# PiezoDriver.net
KiCad netlist of a schematic drawn in EAGLE
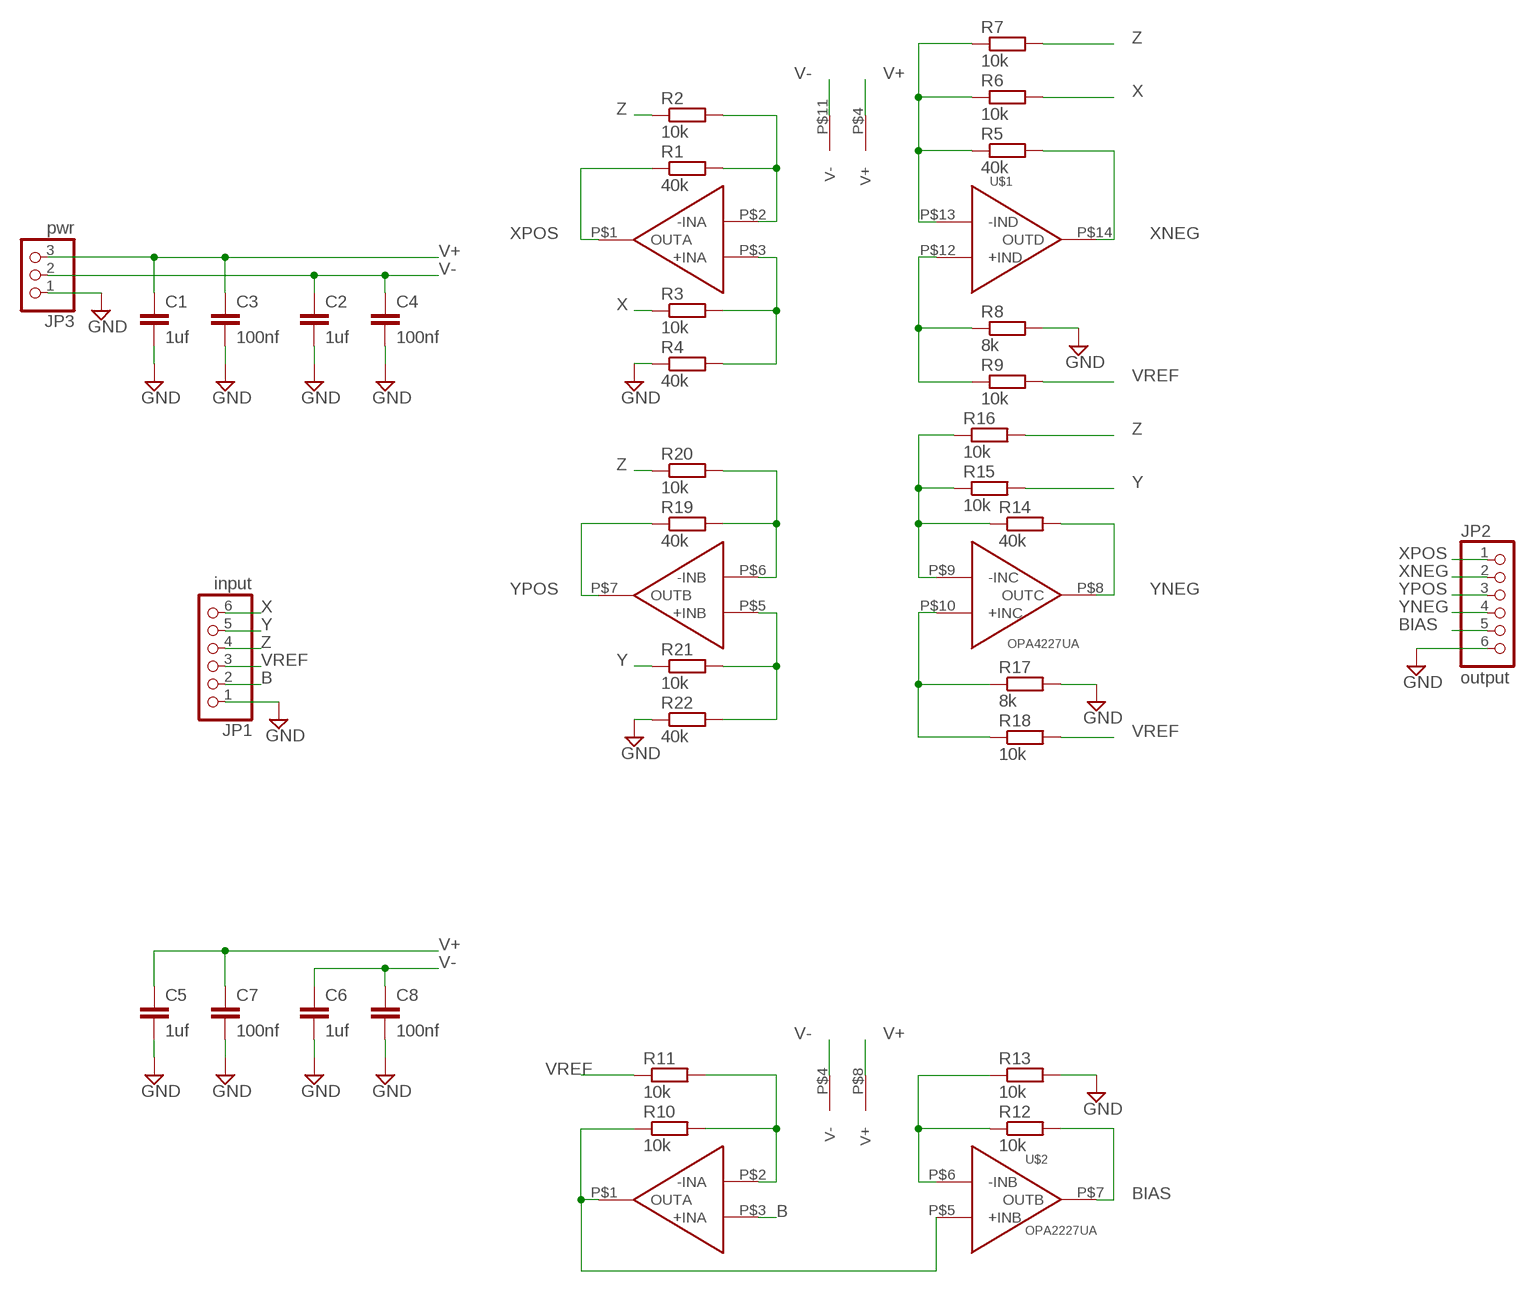
[diagram p0: schematic, sheet 1]

(export (version "E")
  (design (tool "Eeschema 10.0.6"))
  (components
    (comp (ref "C1")
      (value "1uf")
      (footprint "eagle-import:C0603")
      (libsource (lib "eagle-import") (part "C-EUC0603"))
    )
    (comp (ref "C2")
      (value "1uf")
      (footprint "eagle-import:C0603")
      (libsource (lib "eagle-import") (part "C-EUC0603"))
    )
    (comp (ref "C3")
      (value "100nf")
      (footprint "eagle-import:C0603")
      (libsource (lib "eagle-import") (part "C-EUC0603"))
    )
    (comp (ref "C4")
      (value "100nf")
      (footprint "eagle-import:C0603")
      (libsource (lib "eagle-import") (part "C-EUC0603"))
    )
    (comp (ref "C5")
      (value "1uf")
      (footprint "eagle-import:C0603")
      (libsource (lib "eagle-import") (part "C-EUC0603"))
    )
    (comp (ref "C6")
      (value "1uf")
      (footprint "eagle-import:C0603")
      (libsource (lib "eagle-import") (part "C-EUC0603"))
    )
    (comp (ref "C7")
      (value "100nf")
      (footprint "eagle-import:C0603")
      (libsource (lib "eagle-import") (part "C-EUC0603"))
    )
    (comp (ref "C8")
      (value "100nf")
      (footprint "eagle-import:C0603")
      (libsource (lib "eagle-import") (part "C-EUC0603"))
    )
    (comp (ref "JP1")
      (value "input")
      (footprint "eagle-import:1X06")
      (libsource (lib "eagle-import") (part "PINHD-1X6"))
    )
    (comp (ref "JP2")
      (value "output")
      (footprint "eagle-import:1X06")
      (libsource (lib "eagle-import") (part "PINHD-1X6"))
    )
    (comp (ref "JP3")
      (value "pwr")
      (footprint "eagle-import:1X03")
      (libsource (lib "eagle-import") (part "PINHD-1X3"))
    )
    (comp (ref "R1")
      (value "40k")
      (footprint "eagle-import:R0603")
      (libsource (lib "eagle-import") (part "R-EU_R0603"))
    )
    (comp (ref "R2")
      (value "10k")
      (footprint "eagle-import:R0603")
      (libsource (lib "eagle-import") (part "R-EU_R0603"))
    )
    (comp (ref "R3")
      (value "10k")
      (footprint "eagle-import:R0603")
      (libsource (lib "eagle-import") (part "R-EU_R0603"))
    )
    (comp (ref "R4")
      (value "40k")
      (footprint "eagle-import:R0603")
      (libsource (lib "eagle-import") (part "R-EU_R0603"))
    )
    (comp (ref "R5")
      (value "40k")
      (footprint "eagle-import:R0603")
      (libsource (lib "eagle-import") (part "R-EU_R0603"))
    )
    (comp (ref "R6")
      (value "10k")
      (footprint "eagle-import:R0603")
      (libsource (lib "eagle-import") (part "R-EU_R0603"))
    )
    (comp (ref "R7")
      (value "10k")
      (footprint "eagle-import:R0603")
      (libsource (lib "eagle-import") (part "R-EU_R0603"))
    )
    (comp (ref "R8")
      (value "8k")
      (footprint "eagle-import:R0603")
      (libsource (lib "eagle-import") (part "R-EU_R0603"))
    )
    (comp (ref "R9")
      (value "10k")
      (footprint "eagle-import:R0603")
      (libsource (lib "eagle-import") (part "R-EU_R0603"))
    )
    (comp (ref "R10")
      (value "10k")
      (footprint "eagle-import:R0603")
      (libsource (lib "eagle-import") (part "R-EU_R0603"))
    )
    (comp (ref "R11")
      (value "10k")
      (footprint "eagle-import:R0603")
      (libsource (lib "eagle-import") (part "R-EU_R0603"))
    )
    (comp (ref "R12")
      (value "10k")
      (footprint "eagle-import:R0603")
      (libsource (lib "eagle-import") (part "R-EU_R0603"))
    )
    (comp (ref "R13")
      (value "10k")
      (footprint "eagle-import:R0603")
      (libsource (lib "eagle-import") (part "R-EU_R0603"))
    )
    (comp (ref "R14")
      (value "40k")
      (footprint "eagle-import:R0603")
      (libsource (lib "eagle-import") (part "R-EU_R0603"))
    )
    (comp (ref "R15")
      (value "10k")
      (footprint "eagle-import:R0603")
      (libsource (lib "eagle-import") (part "R-EU_R0603"))
    )
    (comp (ref "R16")
      (value "10k")
      (footprint "eagle-import:R0603")
      (libsource (lib "eagle-import") (part "R-EU_R0603"))
    )
    (comp (ref "R17")
      (value "8k")
      (footprint "eagle-import:R0603")
      (libsource (lib "eagle-import") (part "R-EU_R0603"))
    )
    (comp (ref "R18")
      (value "10k")
      (footprint "eagle-import:R0603")
      (libsource (lib "eagle-import") (part "R-EU_R0603"))
    )
    (comp (ref "R19")
      (value "40k")
      (footprint "eagle-import:R0603")
      (libsource (lib "eagle-import") (part "R-EU_R0603"))
    )
    (comp (ref "R20")
      (value "10k")
      (footprint "eagle-import:R0603")
      (libsource (lib "eagle-import") (part "R-EU_R0603"))
    )
    (comp (ref "R21")
      (value "10k")
      (footprint "eagle-import:R0603")
      (libsource (lib "eagle-import") (part "R-EU_R0603"))
    )
    (comp (ref "R22")
      (value "40k")
      (footprint "eagle-import:R0603")
      (libsource (lib "eagle-import") (part "R-EU_R0603"))
    )
    (comp (ref "U$1")
      (value "OPA4227UA")
      (footprint "eagle-import:SOIC-14")
      (libsource (lib "eagle-import") (part "OPA4227UA"))
    )
    (comp (ref "U$2")
      (value "OPA2227UA")
      (footprint "eagle-import:SOIC-8")
      (libsource (lib "eagle-import") (part "OPA2227UA"))
    )
  )
  (nets
    (net (code "1") (name "/B") (class "Default")
      (node (ref "JP1") (pin "2") (pinfunction "2_2") (pintype "passive"))
      (node (ref "U$2") (pin "P$3") (pinfunction "+INA_P$3") (pintype "input"))
    )
    (net (code "2") (name "/BIAS") (class "Default")
      (node (ref "JP2") (pin "5") (pinfunction "5_5") (pintype "passive"))
      (node (ref "R12") (pin "2") (pinfunction "2_2") (pintype "passive"))
      (node (ref "U$2") (pin "P$7") (pinfunction "OUTB_P$7") (pintype "output"))
    )
    (net (code "3") (name "/V+") (class "Default")
      (node (ref "C1") (pin "1") (pinfunction "1_1") (pintype "passive"))
      (node (ref "C3") (pin "1") (pinfunction "1_1") (pintype "passive"))
      (node (ref "C5") (pin "1") (pinfunction "1_1") (pintype "passive"))
      (node (ref "C7") (pin "1") (pinfunction "1_1") (pintype "passive"))
      (node (ref "JP3") (pin "3") (pinfunction "3_3") (pintype "passive"))
      (node (ref "U$1") (pin "P$4") (pinfunction "V+_P$4") (pintype "power_in"))
      (node (ref "U$2") (pin "P$8") (pinfunction "V+_P$8") (pintype "power_in"))
    )
    (net (code "4") (name "/V-") (class "Default")
      (node (ref "C2") (pin "1") (pinfunction "1_1") (pintype "passive"))
      (node (ref "C4") (pin "1") (pinfunction "1_1") (pintype "passive"))
      (node (ref "C6") (pin "1") (pinfunction "1_1") (pintype "passive"))
      (node (ref "C8") (pin "1") (pinfunction "1_1") (pintype "passive"))
      (node (ref "JP3") (pin "2") (pinfunction "2_2") (pintype "passive"))
      (node (ref "U$1") (pin "P$11") (pinfunction "V-_P$11") (pintype "power_in"))
      (node (ref "U$2") (pin "P$4") (pinfunction "V-_P$4") (pintype "power_in"))
    )
    (net (code "5") (name "/VREF") (class "Default")
      (node (ref "JP1") (pin "3") (pinfunction "3_3") (pintype "passive"))
      (node (ref "R11") (pin "1") (pinfunction "1_1") (pintype "passive"))
      (node (ref "R18") (pin "2") (pinfunction "2_2") (pintype "passive"))
      (node (ref "R9") (pin "2") (pinfunction "2_2") (pintype "passive"))
    )
    (net (code "6") (name "/X") (class "Default")
      (node (ref "JP1") (pin "6") (pinfunction "6_6") (pintype "passive"))
      (node (ref "R3") (pin "1") (pinfunction "1_1") (pintype "passive"))
      (node (ref "R6") (pin "2") (pinfunction "2_2") (pintype "passive"))
    )
    (net (code "7") (name "/XNEG") (class "Default")
      (node (ref "JP2") (pin "2") (pinfunction "2_2") (pintype "passive"))
      (node (ref "R5") (pin "2") (pinfunction "2_2") (pintype "passive"))
      (node (ref "U$1") (pin "P$14") (pinfunction "OUTD_P$14") (pintype "output"))
    )
    (net (code "8") (name "/XPOS") (class "Default")
      (node (ref "JP2") (pin "1") (pinfunction "1_1") (pintype "passive"))
      (node (ref "R1") (pin "1") (pinfunction "1_1") (pintype "passive"))
      (node (ref "U$1") (pin "P$1") (pinfunction "OUTA_P$1") (pintype "output"))
    )
    (net (code "9") (name "/Y") (class "Default")
      (node (ref "JP1") (pin "5") (pinfunction "5_5") (pintype "passive"))
      (node (ref "R15") (pin "2") (pinfunction "2_2") (pintype "passive"))
      (node (ref "R21") (pin "1") (pinfunction "1_1") (pintype "passive"))
    )
    (net (code "10") (name "/YNEG") (class "Default")
      (node (ref "JP2") (pin "4") (pinfunction "4_4") (pintype "passive"))
      (node (ref "R14") (pin "2") (pinfunction "2_2") (pintype "passive"))
      (node (ref "U$1") (pin "P$8") (pinfunction "OUTC_P$8") (pintype "output"))
    )
    (net (code "11") (name "/YPOS") (class "Default")
      (node (ref "JP2") (pin "3") (pinfunction "3_3") (pintype "passive"))
      (node (ref "R19") (pin "1") (pinfunction "1_1") (pintype "passive"))
      (node (ref "U$1") (pin "P$7") (pinfunction "OUTB_P$7") (pintype "output"))
    )
    (net (code "12") (name "/Z") (class "Default")
      (node (ref "JP1") (pin "4") (pinfunction "4_4") (pintype "passive"))
      (node (ref "R16") (pin "2") (pinfunction "2_2") (pintype "passive"))
      (node (ref "R2") (pin "1") (pinfunction "1_1") (pintype "passive"))
      (node (ref "R20") (pin "1") (pinfunction "1_1") (pintype "passive"))
      (node (ref "R7") (pin "2") (pinfunction "2_2") (pintype "passive"))
    )
    (net (code "13") (name "GND") (class "Default")
      (node (ref "C1") (pin "2") (pinfunction "2_2") (pintype "passive"))
      (node (ref "C2") (pin "2") (pinfunction "2_2") (pintype "passive"))
      (node (ref "C3") (pin "2") (pinfunction "2_2") (pintype "passive"))
      (node (ref "C4") (pin "2") (pinfunction "2_2") (pintype "passive"))
      (node (ref "C5") (pin "2") (pinfunction "2_2") (pintype "passive"))
      (node (ref "C6") (pin "2") (pinfunction "2_2") (pintype "passive"))
      (node (ref "C7") (pin "2") (pinfunction "2_2") (pintype "passive"))
      (node (ref "C8") (pin "2") (pinfunction "2_2") (pintype "passive"))
      (node (ref "JP1") (pin "1") (pinfunction "1_1") (pintype "passive"))
      (node (ref "JP2") (pin "6") (pinfunction "6_6") (pintype "passive"))
      (node (ref "JP3") (pin "1") (pinfunction "1_1") (pintype "passive"))
      (node (ref "R13") (pin "2") (pinfunction "2_2") (pintype "passive"))
      (node (ref "R17") (pin "2") (pinfunction "2_2") (pintype "passive"))
      (node (ref "R22") (pin "1") (pinfunction "1_1") (pintype "passive"))
      (node (ref "R4") (pin "1") (pinfunction "1_1") (pintype "passive"))
      (node (ref "R8") (pin "2") (pinfunction "2_2") (pintype "passive"))
    )
    (net (code "14") (name "Net-(U$1-+INA)") (class "Default")
      (node (ref "R3") (pin "2") (pinfunction "2_2") (pintype "passive"))
      (node (ref "R4") (pin "2") (pinfunction "2_2") (pintype "passive"))
      (node (ref "U$1") (pin "P$3") (pinfunction "+INA_P$3") (pintype "input"))
    )
    (net (code "15") (name "Net-(U$1-+INB)") (class "Default")
      (node (ref "R21") (pin "2") (pinfunction "2_2") (pintype "passive"))
      (node (ref "R22") (pin "2") (pinfunction "2_2") (pintype "passive"))
      (node (ref "U$1") (pin "P$5") (pinfunction "+INB_P$5") (pintype "input"))
    )
    (net (code "16") (name "Net-(U$1-+INC)") (class "Default")
      (node (ref "R17") (pin "1") (pinfunction "1_1") (pintype "passive"))
      (node (ref "R18") (pin "1") (pinfunction "1_1") (pintype "passive"))
      (node (ref "U$1") (pin "P$10") (pinfunction "+INC_P$10") (pintype "input"))
    )
    (net (code "17") (name "Net-(U$1-+IND)") (class "Default")
      (node (ref "R8") (pin "1") (pinfunction "1_1") (pintype "passive"))
      (node (ref "R9") (pin "1") (pinfunction "1_1") (pintype "passive"))
      (node (ref "U$1") (pin "P$12") (pinfunction "+IND_P$12") (pintype "input"))
    )
    (net (code "18") (name "Net-(U$1--INA)") (class "Default")
      (node (ref "R1") (pin "2") (pinfunction "2_2") (pintype "passive"))
      (node (ref "R2") (pin "2") (pinfunction "2_2") (pintype "passive"))
      (node (ref "U$1") (pin "P$2") (pinfunction "-INA_P$2") (pintype "input"))
    )
    (net (code "19") (name "Net-(U$1--INB)") (class "Default")
      (node (ref "R19") (pin "2") (pinfunction "2_2") (pintype "passive"))
      (node (ref "R20") (pin "2") (pinfunction "2_2") (pintype "passive"))
      (node (ref "U$1") (pin "P$6") (pinfunction "-INB_P$6") (pintype "input"))
    )
    (net (code "20") (name "Net-(U$1--INC)") (class "Default")
      (node (ref "R14") (pin "1") (pinfunction "1_1") (pintype "passive"))
      (node (ref "R15") (pin "1") (pinfunction "1_1") (pintype "passive"))
      (node (ref "R16") (pin "1") (pinfunction "1_1") (pintype "passive"))
      (node (ref "U$1") (pin "P$9") (pinfunction "-INC_P$9") (pintype "input"))
    )
    (net (code "21") (name "Net-(U$1--IND)") (class "Default")
      (node (ref "R5") (pin "1") (pinfunction "1_1") (pintype "passive"))
      (node (ref "R6") (pin "1") (pinfunction "1_1") (pintype "passive"))
      (node (ref "R7") (pin "1") (pinfunction "1_1") (pintype "passive"))
      (node (ref "U$1") (pin "P$13") (pinfunction "-IND_P$13") (pintype "input"))
    )
    (net (code "22") (name "Net-(U$2-+INB)") (class "Default")
      (node (ref "R10") (pin "1") (pinfunction "1_1") (pintype "passive"))
      (node (ref "U$2") (pin "P$1") (pinfunction "OUTA_P$1") (pintype "output"))
      (node (ref "U$2") (pin "P$5") (pinfunction "+INB_P$5") (pintype "input"))
    )
    (net (code "23") (name "Net-(U$2--INA)") (class "Default")
      (node (ref "R10") (pin "2") (pinfunction "2_2") (pintype "passive"))
      (node (ref "R11") (pin "2") (pinfunction "2_2") (pintype "passive"))
      (node (ref "U$2") (pin "P$2") (pinfunction "-INA_P$2") (pintype "input"))
    )
    (net (code "24") (name "Net-(U$2--INB)") (class "Default")
      (node (ref "R12") (pin "1") (pinfunction "1_1") (pintype "passive"))
      (node (ref "R13") (pin "1") (pinfunction "1_1") (pintype "passive"))
      (node (ref "U$2") (pin "P$6") (pinfunction "-INB_P$6") (pintype "input"))
    )
  )
)
